# LOGO_LED_board.net
KiCad netlist of a schematic drawn in EAGLE
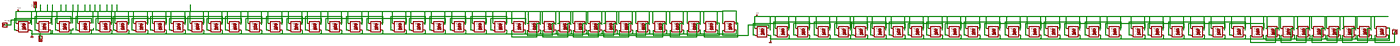
[diagram p0: schematic, sheet 1, overview]
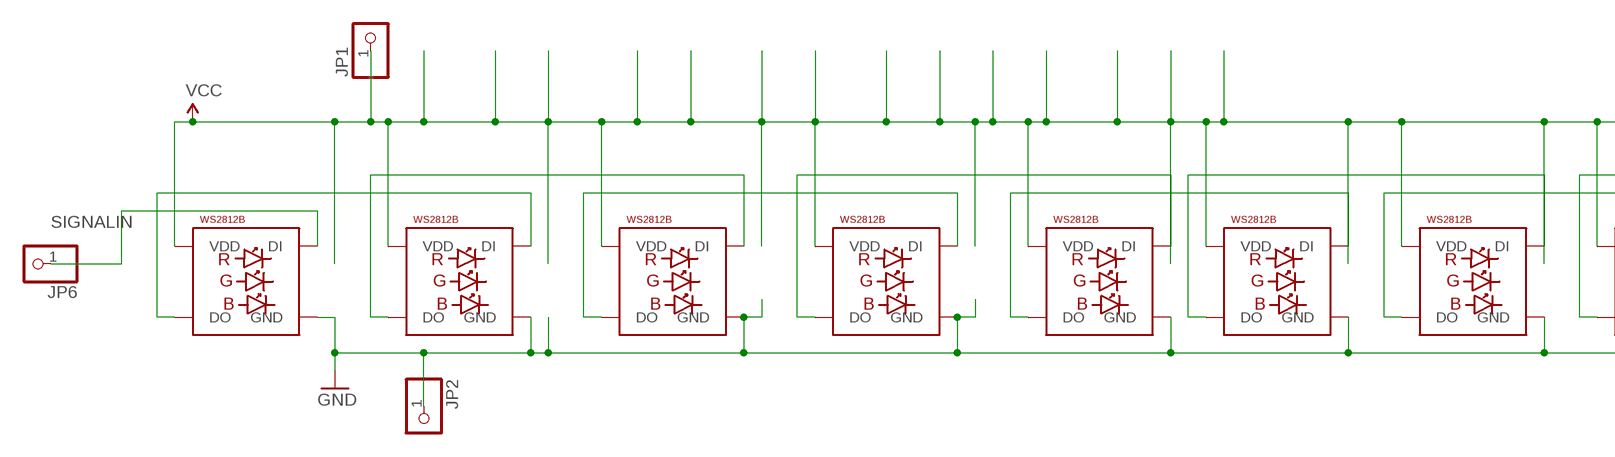
[diagram p1: schematic, sheet 1, part 1 of 8]
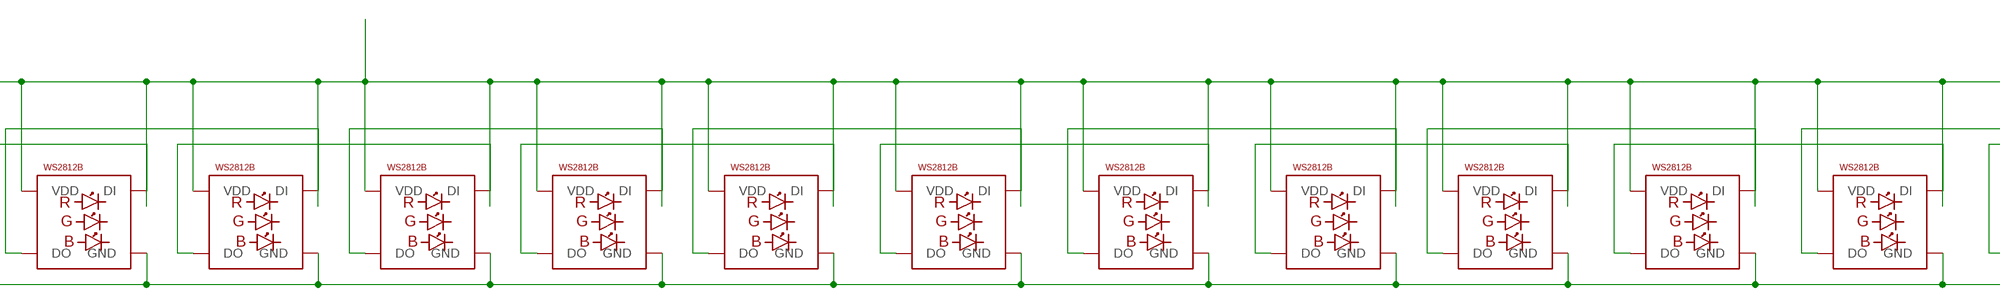
[diagram p2: schematic, sheet 1, part 2 of 8]
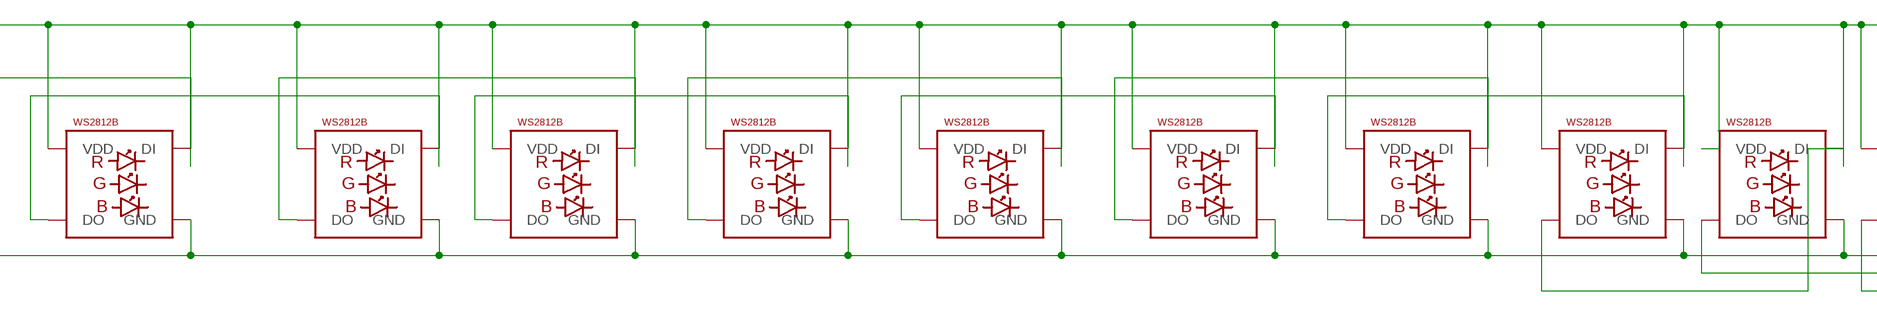
[diagram p3: schematic, sheet 1, part 3 of 8]
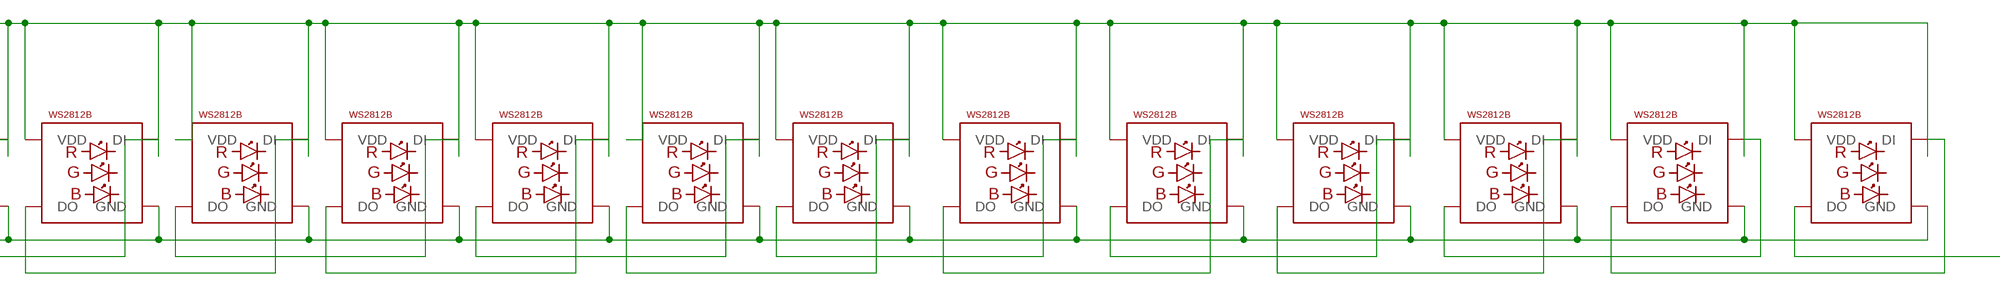
[diagram p4: schematic, sheet 1, part 4 of 8]
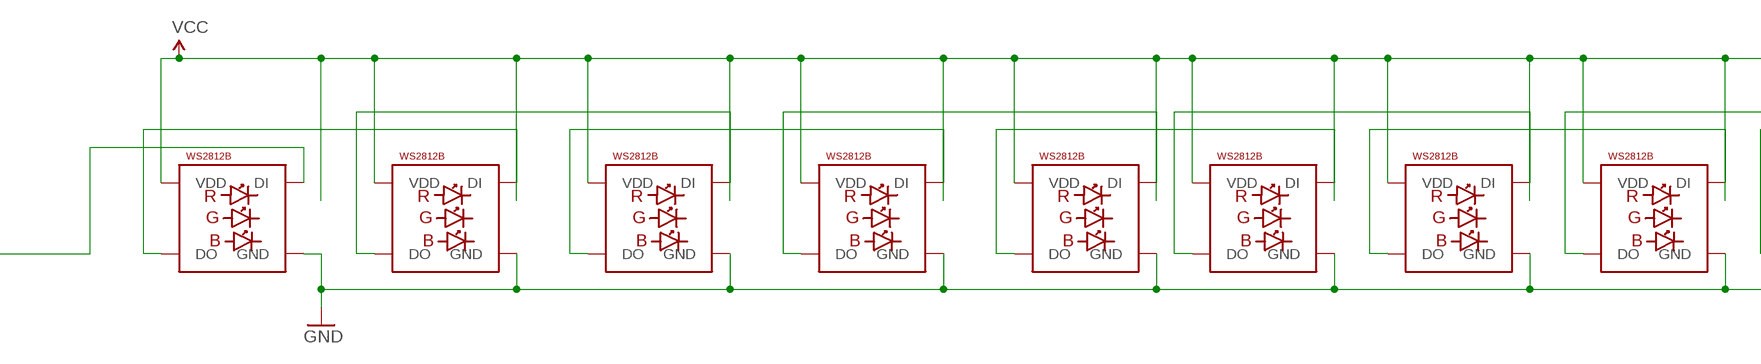
[diagram p5: schematic, sheet 1, part 5 of 8]
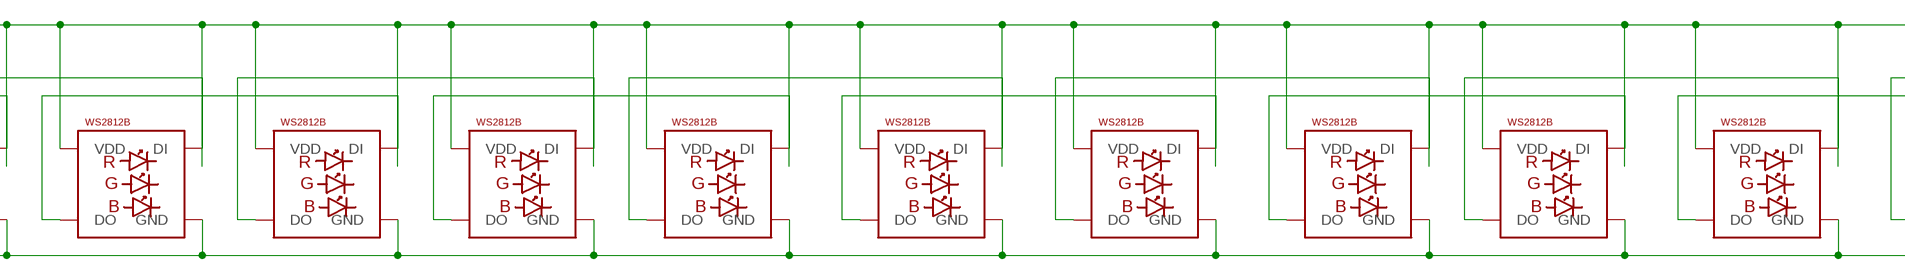
[diagram p6: schematic, sheet 1, part 6 of 8]
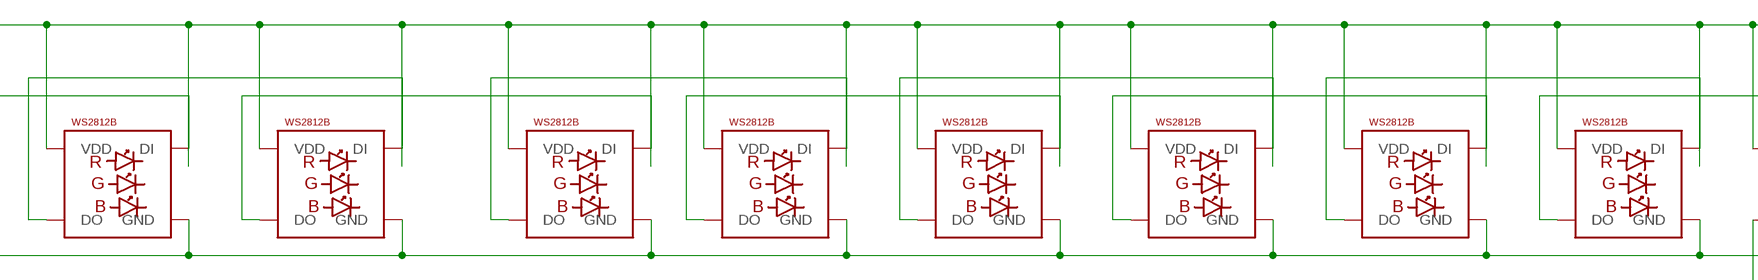
[diagram p7: schematic, sheet 1, part 7 of 8]
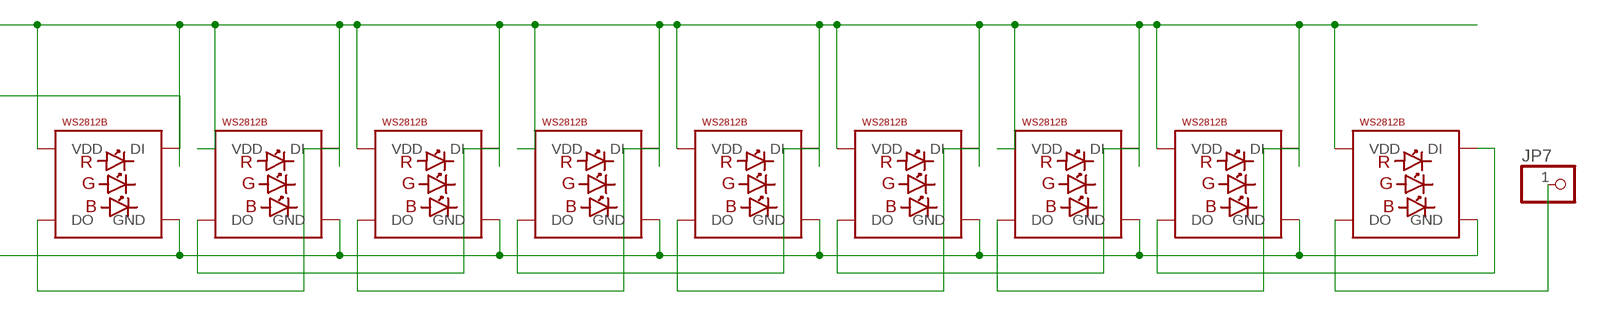
[diagram p8: schematic, sheet 1, part 8 of 8]

(export (version "E")
  (design (tool "Eeschema 10.0.6"))
  (components
    (comp (ref "JP1")
      (value "PINHD-1X1")
      (footprint "eagle-import:1X01")
      (libsource (lib "eagle-import") (part "PINHD-1X1"))
    )
    (comp (ref "JP2")
      (value "PINHD-1X1")
      (footprint "eagle-import:1X01")
      (libsource (lib "eagle-import") (part "PINHD-1X1"))
    )
    (comp (ref "JP6")
      (value "PINHD-1X1")
      (footprint "eagle-import:1X01")
      (libsource (lib "eagle-import") (part "PINHD-1X1"))
    )
    (comp (ref "JP7")
      (value "PINHD-1X1")
      (footprint "eagle-import:1X01")
      (libsource (lib "eagle-import") (part "PINHD-1X1"))
    )
    (comp (ref "LED1")
      (value "WS2812B5050")
      (footprint "eagle-import:WS2812B")
      (libsource (lib "eagle-import") (part "WS2812B5050"))
    )
    (comp (ref "LED2")
      (value "WS2812B5050")
      (footprint "eagle-import:WS2812B")
      (libsource (lib "eagle-import") (part "WS2812B5050"))
    )
    (comp (ref "LED3")
      (value "WS2812B5050")
      (footprint "eagle-import:WS2812B")
      (libsource (lib "eagle-import") (part "WS2812B5050"))
    )
    (comp (ref "LED4")
      (value "WS2812B5050")
      (footprint "eagle-import:WS2812B")
      (libsource (lib "eagle-import") (part "WS2812B5050"))
    )
    (comp (ref "LED5")
      (value "WS2812B5050")
      (footprint "eagle-import:WS2812B")
      (libsource (lib "eagle-import") (part "WS2812B5050"))
    )
    (comp (ref "LED6")
      (value "WS2812B5050")
      (footprint "eagle-import:WS2812B")
      (libsource (lib "eagle-import") (part "WS2812B5050"))
    )
    (comp (ref "LED7")
      (value "WS2812B5050")
      (footprint "eagle-import:WS2812B")
      (libsource (lib "eagle-import") (part "WS2812B5050"))
    )
    (comp (ref "LED8")
      (value "WS2812B5050")
      (footprint "eagle-import:WS2812B")
      (libsource (lib "eagle-import") (part "WS2812B5050"))
    )
    (comp (ref "LED9")
      (value "WS2812B5050")
      (footprint "eagle-import:WS2812B")
      (libsource (lib "eagle-import") (part "WS2812B5050"))
    )
    (comp (ref "LED10")
      (value "WS2812B5050")
      (footprint "eagle-import:WS2812B")
      (libsource (lib "eagle-import") (part "WS2812B5050"))
    )
    (comp (ref "LED11")
      (value "WS2812B5050")
      (footprint "eagle-import:WS2812B")
      (libsource (lib "eagle-import") (part "WS2812B5050"))
    )
    (comp (ref "LED12")
      (value "WS2812B5050")
      (footprint "eagle-import:WS2812B")
      (libsource (lib "eagle-import") (part "WS2812B5050"))
    )
    (comp (ref "LED13")
      (value "WS2812B5050")
      (footprint "eagle-import:WS2812B")
      (libsource (lib "eagle-import") (part "WS2812B5050"))
    )
    (comp (ref "LED14")
      (value "WS2812B5050")
      (footprint "eagle-import:WS2812B")
      (libsource (lib "eagle-import") (part "WS2812B5050"))
    )
    (comp (ref "LED15")
      (value "WS2812B5050")
      (footprint "eagle-import:WS2812B")
      (libsource (lib "eagle-import") (part "WS2812B5050"))
    )
    (comp (ref "LED16")
      (value "WS2812B5050")
      (footprint "eagle-import:WS2812B")
      (libsource (lib "eagle-import") (part "WS2812B5050"))
    )
    (comp (ref "LED17")
      (value "WS2812B5050")
      (footprint "eagle-import:WS2812B")
      (libsource (lib "eagle-import") (part "WS2812B5050"))
    )
    (comp (ref "LED18")
      (value "WS2812B5050")
      (footprint "eagle-import:WS2812B")
      (libsource (lib "eagle-import") (part "WS2812B5050"))
    )
    (comp (ref "LED19")
      (value "WS2812B5050")
      (footprint "eagle-import:WS2812B")
      (libsource (lib "eagle-import") (part "WS2812B5050"))
    )
    (comp (ref "LED20")
      (value "WS2812B5050")
      (footprint "eagle-import:WS2812B")
      (libsource (lib "eagle-import") (part "WS2812B5050"))
    )
    (comp (ref "LED21")
      (value "WS2812B5050")
      (footprint "eagle-import:WS2812B")
      (libsource (lib "eagle-import") (part "WS2812B5050"))
    )
    (comp (ref "LED22")
      (value "WS2812B5050")
      (footprint "eagle-import:WS2812B")
      (libsource (lib "eagle-import") (part "WS2812B5050"))
    )
    (comp (ref "LED23")
      (value "WS2812B5050")
      (footprint "eagle-import:WS2812B")
      (libsource (lib "eagle-import") (part "WS2812B5050"))
    )
    (comp (ref "LED24")
      (value "WS2812B5050")
      (footprint "eagle-import:WS2812B")
      (libsource (lib "eagle-import") (part "WS2812B5050"))
    )
    (comp (ref "LED25")
      (value "WS2812B5050")
      (footprint "eagle-import:WS2812B")
      (libsource (lib "eagle-import") (part "WS2812B5050"))
    )
    (comp (ref "LED26")
      (value "WS2812B5050")
      (footprint "eagle-import:WS2812B")
      (libsource (lib "eagle-import") (part "WS2812B5050"))
    )
    (comp (ref "LED27")
      (value "WS2812B5050")
      (footprint "eagle-import:WS2812B")
      (libsource (lib "eagle-import") (part "WS2812B5050"))
    )
    (comp (ref "LED28")
      (value "WS2812B5050")
      (footprint "eagle-import:WS2812B")
      (libsource (lib "eagle-import") (part "WS2812B5050"))
    )
    (comp (ref "LED29")
      (value "WS2812B5050")
      (footprint "eagle-import:WS2812B")
      (libsource (lib "eagle-import") (part "WS2812B5050"))
    )
    (comp (ref "LED30")
      (value "WS2812B5050")
      (footprint "eagle-import:WS2812B")
      (libsource (lib "eagle-import") (part "WS2812B5050"))
    )
    (comp (ref "LED31")
      (value "WS2812B5050")
      (footprint "eagle-import:WS2812B")
      (libsource (lib "eagle-import") (part "WS2812B5050"))
    )
    (comp (ref "LED32")
      (value "WS2812B5050")
      (footprint "eagle-import:WS2812B")
      (libsource (lib "eagle-import") (part "WS2812B5050"))
    )
    (comp (ref "LED33")
      (value "WS2812B5050")
      (footprint "eagle-import:WS2812B")
      (libsource (lib "eagle-import") (part "WS2812B5050"))
    )
    (comp (ref "LED34")
      (value "WS2812B5050")
      (footprint "eagle-import:WS2812B")
      (libsource (lib "eagle-import") (part "WS2812B5050"))
    )
    (comp (ref "LED35")
      (value "WS2812B5050")
      (footprint "eagle-import:WS2812B")
      (libsource (lib "eagle-import") (part "WS2812B5050"))
    )
    (comp (ref "LED36")
      (value "WS2812B5050")
      (footprint "eagle-import:WS2812B")
      (libsource (lib "eagle-import") (part "WS2812B5050"))
    )
    (comp (ref "LED37")
      (value "WS2812B5050")
      (footprint "eagle-import:WS2812B")
      (libsource (lib "eagle-import") (part "WS2812B5050"))
    )
    (comp (ref "LED38")
      (value "WS2812B5050")
      (footprint "eagle-import:WS2812B")
      (libsource (lib "eagle-import") (part "WS2812B5050"))
    )
    (comp (ref "LED39")
      (value "WS2812B5050")
      (footprint "eagle-import:WS2812B")
      (libsource (lib "eagle-import") (part "WS2812B5050"))
    )
    (comp (ref "LED40")
      (value "WS2812B5050")
      (footprint "eagle-import:WS2812B")
      (libsource (lib "eagle-import") (part "WS2812B5050"))
    )
    (comp (ref "LED41")
      (value "WS2812B5050")
      (footprint "eagle-import:WS2812B")
      (libsource (lib "eagle-import") (part "WS2812B5050"))
    )
    (comp (ref "LED42")
      (value "WS2812B5050")
      (footprint "eagle-import:WS2812B")
      (libsource (lib "eagle-import") (part "WS2812B5050"))
    )
    (comp (ref "LED43")
      (value "WS2812B5050")
      (footprint "eagle-import:WS2812B")
      (libsource (lib "eagle-import") (part "WS2812B5050"))
    )
    (comp (ref "LED44")
      (value "WS2812B5050")
      (footprint "eagle-import:WS2812B")
      (libsource (lib "eagle-import") (part "WS2812B5050"))
    )
    (comp (ref "LED45")
      (value "WS2812B5050")
      (footprint "eagle-import:WS2812B")
      (libsource (lib "eagle-import") (part "WS2812B5050"))
    )
    (comp (ref "LED46")
      (value "WS2812B5050")
      (footprint "eagle-import:WS2812B")
      (libsource (lib "eagle-import") (part "WS2812B5050"))
    )
    (comp (ref "LED47")
      (value "WS2812B5050")
      (footprint "eagle-import:WS2812B")
      (libsource (lib "eagle-import") (part "WS2812B5050"))
    )
    (comp (ref "LED48")
      (value "WS2812B5050")
      (footprint "eagle-import:WS2812B")
      (libsource (lib "eagle-import") (part "WS2812B5050"))
    )
    (comp (ref "LED49")
      (value "WS2812B5050")
      (footprint "eagle-import:WS2812B")
      (libsource (lib "eagle-import") (part "WS2812B5050"))
    )
    (comp (ref "LED50")
      (value "WS2812B5050")
      (footprint "eagle-import:WS2812B")
      (libsource (lib "eagle-import") (part "WS2812B5050"))
    )
    (comp (ref "LED51")
      (value "WS2812B5050")
      (footprint "eagle-import:WS2812B")
      (libsource (lib "eagle-import") (part "WS2812B5050"))
    )
    (comp (ref "LED52")
      (value "WS2812B5050")
      (footprint "eagle-import:WS2812B")
      (libsource (lib "eagle-import") (part "WS2812B5050"))
    )
    (comp (ref "LED53")
      (value "WS2812B5050")
      (footprint "eagle-import:WS2812B")
      (libsource (lib "eagle-import") (part "WS2812B5050"))
    )
    (comp (ref "LED54")
      (value "WS2812B5050")
      (footprint "eagle-import:WS2812B")
      (libsource (lib "eagle-import") (part "WS2812B5050"))
    )
    (comp (ref "LED55")
      (value "WS2812B5050")
      (footprint "eagle-import:WS2812B")
      (libsource (lib "eagle-import") (part "WS2812B5050"))
    )
    (comp (ref "LED56")
      (value "WS2812B5050")
      (footprint "eagle-import:WS2812B")
      (libsource (lib "eagle-import") (part "WS2812B5050"))
    )
    (comp (ref "LED57")
      (value "WS2812B5050")
      (footprint "eagle-import:WS2812B")
      (libsource (lib "eagle-import") (part "WS2812B5050"))
    )
    (comp (ref "LED58")
      (value "WS2812B5050")
      (footprint "eagle-import:WS2812B")
      (libsource (lib "eagle-import") (part "WS2812B5050"))
    )
    (comp (ref "LED59")
      (value "WS2812B5050")
      (footprint "eagle-import:WS2812B")
      (libsource (lib "eagle-import") (part "WS2812B5050"))
    )
    (comp (ref "LED60")
      (value "WS2812B5050")
      (footprint "eagle-import:WS2812B")
      (libsource (lib "eagle-import") (part "WS2812B5050"))
    )
    (comp (ref "LED61")
      (value "WS2812B5050")
      (footprint "eagle-import:WS2812B")
      (libsource (lib "eagle-import") (part "WS2812B5050"))
    )
    (comp (ref "LED62")
      (value "WS2812B5050")
      (footprint "eagle-import:WS2812B")
      (libsource (lib "eagle-import") (part "WS2812B5050"))
    )
    (comp (ref "LED63")
      (value "WS2812B5050")
      (footprint "eagle-import:WS2812B")
      (libsource (lib "eagle-import") (part "WS2812B5050"))
    )
    (comp (ref "LED64")
      (value "WS2812B5050")
      (footprint "eagle-import:WS2812B")
      (libsource (lib "eagle-import") (part "WS2812B5050"))
    )
    (comp (ref "LED65")
      (value "WS2812B5050")
      (footprint "eagle-import:WS2812B")
      (libsource (lib "eagle-import") (part "WS2812B5050"))
    )
    (comp (ref "LED66")
      (value "WS2812B5050")
      (footprint "eagle-import:WS2812B")
      (libsource (lib "eagle-import") (part "WS2812B5050"))
    )
    (comp (ref "LED67")
      (value "WS2812B5050")
      (footprint "eagle-import:WS2812B")
      (libsource (lib "eagle-import") (part "WS2812B5050"))
    )
    (comp (ref "LED68")
      (value "WS2812B5050")
      (footprint "eagle-import:WS2812B")
      (libsource (lib "eagle-import") (part "WS2812B5050"))
    )
    (comp (ref "LED69")
      (value "WS2812B5050")
      (footprint "eagle-import:WS2812B")
      (libsource (lib "eagle-import") (part "WS2812B5050"))
    )
    (comp (ref "LED70")
      (value "WS2812B5050")
      (footprint "eagle-import:WS2812B")
      (libsource (lib "eagle-import") (part "WS2812B5050"))
    )
    (comp (ref "LED71")
      (value "WS2812B5050")
      (footprint "eagle-import:WS2812B")
      (libsource (lib "eagle-import") (part "WS2812B5050"))
    )
    (comp (ref "LED72")
      (value "WS2812B5050")
      (footprint "eagle-import:WS2812B")
      (libsource (lib "eagle-import") (part "WS2812B5050"))
    )
    (comp (ref "LED73")
      (value "WS2812B5050")
      (footprint "eagle-import:WS2812B")
      (libsource (lib "eagle-import") (part "WS2812B5050"))
    )
  )
  (nets
    (net (code "1") (name "/SIGNALIN") (class "Default")
      (node (ref "JP6") (pin "1") (pinfunction "1_1") (pintype "passive"))
      (node (ref "LED1") (pin "4-DIN") (pinfunction "DI_4-DIN") (pintype "input"))
    )
    (net (code "2") (name "GND") (class "Default")
      (node (ref "JP2") (pin "1") (pinfunction "1_1") (pintype "passive"))
      (node (ref "LED1") (pin "3-GND") (pinfunction "GND_3-GND") (pintype "power_in"))
      (node (ref "LED10") (pin "3-GND") (pinfunction "GND_3-GND") (pintype "power_in"))
      (node (ref "LED11") (pin "3-GND") (pinfunction "GND_3-GND") (pintype "power_in"))
      (node (ref "LED12") (pin "3-GND") (pinfunction "GND_3-GND") (pintype "power_in"))
      (node (ref "LED13") (pin "3-GND") (pinfunction "GND_3-GND") (pintype "power_in"))
      (node (ref "LED14") (pin "3-GND") (pinfunction "GND_3-GND") (pintype "power_in"))
      (node (ref "LED15") (pin "3-GND") (pinfunction "GND_3-GND") (pintype "power_in"))
      (node (ref "LED16") (pin "3-GND") (pinfunction "GND_3-GND") (pintype "power_in"))
      (node (ref "LED17") (pin "3-GND") (pinfunction "GND_3-GND") (pintype "power_in"))
      (node (ref "LED18") (pin "3-GND") (pinfunction "GND_3-GND") (pintype "power_in"))
      (node (ref "LED19") (pin "3-GND") (pinfunction "GND_3-GND") (pintype "power_in"))
      (node (ref "LED2") (pin "3-GND") (pinfunction "GND_3-GND") (pintype "power_in"))
      (node (ref "LED20") (pin "3-GND") (pinfunction "GND_3-GND") (pintype "power_in"))
      (node (ref "LED21") (pin "3-GND") (pinfunction "GND_3-GND") (pintype "power_in"))
      (node (ref "LED22") (pin "3-GND") (pinfunction "GND_3-GND") (pintype "power_in"))
      (node (ref "LED23") (pin "3-GND") (pinfunction "GND_3-GND") (pintype "power_in"))
      (node (ref "LED24") (pin "3-GND") (pinfunction "GND_3-GND") (pintype "power_in"))
      (node (ref "LED25") (pin "3-GND") (pinfunction "GND_3-GND") (pintype "power_in"))
      (node (ref "LED26") (pin "3-GND") (pinfunction "GND_3-GND") (pintype "power_in"))
      (node (ref "LED27") (pin "3-GND") (pinfunction "GND_3-GND") (pintype "power_in"))
      (node (ref "LED28") (pin "3-GND") (pinfunction "GND_3-GND") (pintype "power_in"))
      (node (ref "LED29") (pin "3-GND") (pinfunction "GND_3-GND") (pintype "power_in"))
      (node (ref "LED3") (pin "3-GND") (pinfunction "GND_3-GND") (pintype "power_in"))
      (node (ref "LED30") (pin "3-GND") (pinfunction "GND_3-GND") (pintype "power_in"))
      (node (ref "LED31") (pin "3-GND") (pinfunction "GND_3-GND") (pintype "power_in"))
      (node (ref "LED32") (pin "3-GND") (pinfunction "GND_3-GND") (pintype "power_in"))
      (node (ref "LED33") (pin "3-GND") (pinfunction "GND_3-GND") (pintype "power_in"))
      (node (ref "LED34") (pin "3-GND") (pinfunction "GND_3-GND") (pintype "power_in"))
      (node (ref "LED35") (pin "3-GND") (pinfunction "GND_3-GND") (pintype "power_in"))
      (node (ref "LED36") (pin "3-GND") (pinfunction "GND_3-GND") (pintype "power_in"))
      (node (ref "LED37") (pin "3-GND") (pinfunction "GND_3-GND") (pintype "power_in"))
      (node (ref "LED38") (pin "3-GND") (pinfunction "GND_3-GND") (pintype "power_in"))
      (node (ref "LED39") (pin "3-GND") (pinfunction "GND_3-GND") (pintype "power_in"))
      (node (ref "LED4") (pin "3-GND") (pinfunction "GND_3-GND") (pintype "power_in"))
      (node (ref "LED40") (pin "3-GND") (pinfunction "GND_3-GND") (pintype "power_in"))
      (node (ref "LED41") (pin "3-GND") (pinfunction "GND_3-GND") (pintype "power_in"))
      (node (ref "LED42") (pin "3-GND") (pinfunction "GND_3-GND") (pintype "power_in"))
      (node (ref "LED43") (pin "3-GND") (pinfunction "GND_3-GND") (pintype "power_in"))
      (node (ref "LED44") (pin "3-GND") (pinfunction "GND_3-GND") (pintype "power_in"))
      (node (ref "LED45") (pin "3-GND") (pinfunction "GND_3-GND") (pintype "power_in"))
      (node (ref "LED46") (pin "3-GND") (pinfunction "GND_3-GND") (pintype "power_in"))
      (node (ref "LED47") (pin "3-GND") (pinfunction "GND_3-GND") (pintype "power_in"))
      (node (ref "LED48") (pin "3-GND") (pinfunction "GND_3-GND") (pintype "power_in"))
      (node (ref "LED49") (pin "3-GND") (pinfunction "GND_3-GND") (pintype "power_in"))
      (node (ref "LED5") (pin "3-GND") (pinfunction "GND_3-GND") (pintype "power_in"))
      (node (ref "LED50") (pin "3-GND") (pinfunction "GND_3-GND") (pintype "power_in"))
      (node (ref "LED51") (pin "3-GND") (pinfunction "GND_3-GND") (pintype "power_in"))
      (node (ref "LED52") (pin "3-GND") (pinfunction "GND_3-GND") (pintype "power_in"))
      (node (ref "LED53") (pin "3-GND") (pinfunction "GND_3-GND") (pintype "power_in"))
      (node (ref "LED54") (pin "3-GND") (pinfunction "GND_3-GND") (pintype "power_in"))
      (node (ref "LED55") (pin "3-GND") (pinfunction "GND_3-GND") (pintype "power_in"))
      (node (ref "LED56") (pin "3-GND") (pinfunction "GND_3-GND") (pintype "power_in"))
      (node (ref "LED57") (pin "3-GND") (pinfunction "GND_3-GND") (pintype "power_in"))
      (node (ref "LED58") (pin "3-GND") (pinfunction "GND_3-GND") (pintype "power_in"))
      (node (ref "LED59") (pin "3-GND") (pinfunction "GND_3-GND") (pintype "power_in"))
      (node (ref "LED6") (pin "3-GND") (pinfunction "GND_3-GND") (pintype "power_in"))
      (node (ref "LED60") (pin "3-GND") (pinfunction "GND_3-GND") (pintype "power_in"))
      (node (ref "LED61") (pin "3-GND") (pinfunction "GND_3-GND") (pintype "power_in"))
      (node (ref "LED62") (pin "3-GND") (pinfunction "GND_3-GND") (pintype "power_in"))
      (node (ref "LED63") (pin "3-GND") (pinfunction "GND_3-GND") (pintype "power_in"))
      (node (ref "LED64") (pin "3-GND") (pinfunction "GND_3-GND") (pintype "power_in"))
      (node (ref "LED65") (pin "3-GND") (pinfunction "GND_3-GND") (pintype "power_in"))
      (node (ref "LED66") (pin "3-GND") (pinfunction "GND_3-GND") (pintype "power_in"))
      (node (ref "LED67") (pin "3-GND") (pinfunction "GND_3-GND") (pintype "power_in"))
      (node (ref "LED68") (pin "3-GND") (pinfunction "GND_3-GND") (pintype "power_in"))
      (node (ref "LED69") (pin "3-GND") (pinfunction "GND_3-GND") (pintype "power_in"))
      (node (ref "LED7") (pin "3-GND") (pinfunction "GND_3-GND") (pintype "power_in"))
      (node (ref "LED70") (pin "3-GND") (pinfunction "GND_3-GND") (pintype "power_in"))
      (node (ref "LED71") (pin "3-GND") (pinfunction "GND_3-GND") (pintype "power_in"))
      (node (ref "LED72") (pin "3-GND") (pinfunction "GND_3-GND") (pintype "power_in"))
      (node (ref "LED73") (pin "3-GND") (pinfunction "GND_3-GND") (pintype "power_in"))
      (node (ref "LED8") (pin "3-GND") (pinfunction "GND_3-GND") (pintype "power_in"))
      (node (ref "LED9") (pin "3-GND") (pinfunction "GND_3-GND") (pintype "power_in"))
    )
    (net (code "3") (name "Net-(LED1-DO)") (class "Default")
      (node (ref "LED1") (pin "2-DOUT") (pinfunction "DO_2-DOUT") (pintype "output"))
      (node (ref "LED2") (pin "4-DIN") (pinfunction "DI_4-DIN") (pintype "input"))
    )
    (net (code "4") (name "Net-(LED2-DO)") (class "Default")
      (node (ref "LED2") (pin "2-DOUT") (pinfunction "DO_2-DOUT") (pintype "output"))
      (node (ref "LED3") (pin "4-DIN") (pinfunction "DI_4-DIN") (pintype "input"))
    )
    (net (code "5") (name "Net-(LED3-DO)") (class "Default")
      (node (ref "LED3") (pin "2-DOUT") (pinfunction "DO_2-DOUT") (pintype "output"))
      (node (ref "LED4") (pin "4-DIN") (pinfunction "DI_4-DIN") (pintype "input"))
    )
    (net (code "6") (name "Net-(LED4-DO)") (class "Default")
      (node (ref "LED4") (pin "2-DOUT") (pinfunction "DO_2-DOUT") (pintype "output"))
      (node (ref "LED5") (pin "4-DIN") (pinfunction "DI_4-DIN") (pintype "input"))
    )
    (net (code "7") (name "Net-(LED5-DO)") (class "Default")
      (node (ref "LED5") (pin "2-DOUT") (pinfunction "DO_2-DOUT") (pintype "output"))
      (node (ref "LED6") (pin "4-DIN") (pinfunction "DI_4-DIN") (pintype "input"))
    )
    (net (code "8") (name "Net-(LED6-DO)") (class "Default")
      (node (ref "LED6") (pin "2-DOUT") (pinfunction "DO_2-DOUT") (pintype "output"))
      (node (ref "LED7") (pin "4-DIN") (pinfunction "DI_4-DIN") (pintype "input"))
    )
    (net (code "9") (name "Net-(LED7-DO)") (class "Default")
      (node (ref "LED7") (pin "2-DOUT") (pinfunction "DO_2-DOUT") (pintype "output"))
      (node (ref "LED8") (pin "4-DIN") (pinfunction "DI_4-DIN") (pintype "input"))
    )
    (net (code "10") (name "Net-(LED8-DO)") (class "Default")
      (node (ref "LED8") (pin "2-DOUT") (pinfunction "DO_2-DOUT") (pintype "output"))
      (node (ref "LED9") (pin "4-DIN") (pinfunction "DI_4-DIN") (pintype "input"))
    )
    (net (code "11") (name "Net-(LED10-DI)") (class "Default")
      (node (ref "LED10") (pin "4-DIN") (pinfunction "DI_4-DIN") (pintype "input"))
      (node (ref "LED9") (pin "2-DOUT") (pinfunction "DO_2-DOUT") (pintype "output"))
    )
    (net (code "12") (name "Net-(LED10-DO)") (class "Default")
      (node (ref "LED10") (pin "2-DOUT") (pinfunction "DO_2-DOUT") (pintype "output"))
      (node (ref "LED11") (pin "4-DIN") (pinfunction "DI_4-DIN") (pintype "input"))
    )
    (net (code "13") (name "Net-(LED11-DO)") (class "Default")
      (node (ref "LED11") (pin "2-DOUT") (pinfunction "DO_2-DOUT") (pintype "output"))
      (node (ref "LED12") (pin "4-DIN") (pinfunction "DI_4-DIN") (pintype "input"))
    )
    (net (code "14") (name "Net-(LED12-DO)") (class "Default")
      (node (ref "LED12") (pin "2-DOUT") (pinfunction "DO_2-DOUT") (pintype "output"))
      (node (ref "LED13") (pin "4-DIN") (pinfunction "DI_4-DIN") (pintype "input"))
    )
    (net (code "15") (name "Net-(LED13-DO)") (class "Default")
      (node (ref "LED13") (pin "2-DOUT") (pinfunction "DO_2-DOUT") (pintype "output"))
      (node (ref "LED14") (pin "4-DIN") (pinfunction "DI_4-DIN") (pintype "input"))
    )
    (net (code "16") (name "Net-(LED14-DO)") (class "Default")
      (node (ref "LED14") (pin "2-DOUT") (pinfunction "DO_2-DOUT") (pintype "output"))
      (node (ref "LED15") (pin "4-DIN") (pinfunction "DI_4-DIN") (pintype "input"))
    )
    (net (code "17") (name "Net-(LED15-DO)") (class "Default")
      (node (ref "LED15") (pin "2-DOUT") (pinfunction "DO_2-DOUT") (pintype "output"))
      (node (ref "LED16") (pin "4-DIN") (pinfunction "DI_4-DIN") (pintype "input"))
    )
    (net (code "18") (name "Net-(LED16-DO)") (class "Default")
      (node (ref "LED16") (pin "2-DOUT") (pinfunction "DO_2-DOUT") (pintype "output"))
      (node (ref "LED17") (pin "4-DIN") (pinfunction "DI_4-DIN") (pintype "input"))
    )
    (net (code "19") (name "Net-(LED17-DO)") (class "Default")
      (node (ref "LED17") (pin "2-DOUT") (pinfunction "DO_2-DOUT") (pintype "output"))
      (node (ref "LED18") (pin "4-DIN") (pinfunction "DI_4-DIN") (pintype "input"))
    )
    (net (code "20") (name "Net-(LED18-DO)") (class "Default")
      (node (ref "LED18") (pin "2-DOUT") (pinfunction "DO_2-DOUT") (pintype "output"))
      (node (ref "LED19") (pin "4-DIN") (pinfunction "DI_4-DIN") (pintype "input"))
    )
    (net (code "21") (name "Net-(LED19-DO)") (class "Default")
      (node (ref "LED19") (pin "2-DOUT") (pinfunction "DO_2-DOUT") (pintype "output"))
      (node (ref "LED20") (pin "4-DIN") (pinfunction "DI_4-DIN") (pintype "input"))
    )
    (net (code "22") (name "Net-(LED20-DO)") (class "Default")
      (node (ref "LED20") (pin "2-DOUT") (pinfunction "DO_2-DOUT") (pintype "output"))
      (node (ref "LED21") (pin "4-DIN") (pinfunction "DI_4-DIN") (pintype "input"))
    )
    (net (code "23") (name "Net-(LED21-DO)") (class "Default")
      (node (ref "LED21") (pin "2-DOUT") (pinfunction "DO_2-DOUT") (pintype "output"))
      (node (ref "LED22") (pin "4-DIN") (pinfunction "DI_4-DIN") (pintype "input"))
    )
    (net (code "24") (name "Net-(LED22-DO)") (class "Default")
      (node (ref "LED22") (pin "2-DOUT") (pinfunction "DO_2-DOUT") (pintype "output"))
      (node (ref "LED23") (pin "4-DIN") (pinfunction "DI_4-DIN") (pintype "input"))
    )
    (net (code "25") (name "Net-(LED23-DO)") (class "Default")
      (node (ref "LED23") (pin "2-DOUT") (pinfunction "DO_2-DOUT") (pintype "output"))
      (node (ref "LED24") (pin "4-DIN") (pinfunction "DI_4-DIN") (pintype "input"))
    )
    (net (code "26") (name "Net-(LED24-DO)") (class "Default")
      (node (ref "LED24") (pin "2-DOUT") (pinfunction "DO_2-DOUT") (pintype "output"))
      (node (ref "LED25") (pin "4-DIN") (pinfunction "DI_4-DIN") (pintype "input"))
    )
    (net (code "27") (name "Net-(LED25-DO)") (class "Default")
      (node (ref "LED25") (pin "2-DOUT") (pinfunction "DO_2-DOUT") (pintype "output"))
      (node (ref "LED26") (pin "4-DIN") (pinfunction "DI_4-DIN") (pintype "input"))
    )
    (net (code "28") (name "Net-(LED26-DO)") (class "Default")
      (node (ref "LED26") (pin "2-DOUT") (pinfunction "DO_2-DOUT") (pintype "output"))
      (node (ref "LED27") (pin "4-DIN") (pinfunction "DI_4-DIN") (pintype "input"))
    )
    (net (code "29") (name "Net-(LED27-DO)") (class "Default")
      (node (ref "LED27") (pin "2-DOUT") (pinfunction "DO_2-DOUT") (pintype "output"))
      (node (ref "LED28") (pin "4-DIN") (pinfunction "DI_4-DIN") (pintype "input"))
    )
    (net (code "30") (name "Net-(LED28-DO)") (class "Default")
      (node (ref "LED28") (pin "2-DOUT") (pinfunction "DO_2-DOUT") (pintype "output"))
      (node (ref "LED29") (pin "4-DIN") (pinfunction "DI_4-DIN") (pintype "input"))
    )
    (net (code "31") (name "Net-(LED29-DO)") (class "Default")
      (node (ref "LED29") (pin "2-DOUT") (pinfunction "DO_2-DOUT") (pintype "output"))
      (node (ref "LED30") (pin "4-DIN") (pinfunction "DI_4-DIN") (pintype "input"))
    )
    (net (code "32") (name "Net-(LED30-DO)") (class "Default")
      (node (ref "LED30") (pin "2-DOUT") (pinfunction "DO_2-DOUT") (pintype "output"))
      (node (ref "LED31") (pin "4-DIN") (pinfunction "DI_4-DIN") (pintype "input"))
    )
    (net (code "33") (name "Net-(LED31-DO)") (class "Default")
      (node (ref "LED31") (pin "2-DOUT") (pinfunction "DO_2-DOUT") (pintype "output"))
      (node (ref "LED32") (pin "4-DIN") (pinfunction "DI_4-DIN") (pintype "input"))
    )
    (net (code "34") (name "Net-(LED32-DO)") (class "Default")
      (node (ref "LED32") (pin "2-DOUT") (pinfunction "DO_2-DOUT") (pintype "output"))
      (node (ref "LED33") (pin "4-DIN") (pinfunction "DI_4-DIN") (pintype "input"))
    )
    (net (code "35") (name "Net-(LED33-DO)") (class "Default")
      (node (ref "LED33") (pin "2-DOUT") (pinfunction "DO_2-DOUT") (pintype "output"))
      (node (ref "LED34") (pin "4-DIN") (pinfunction "DI_4-DIN") (pintype "input"))
    )
    (net (code "36") (name "Net-(LED34-DO)") (class "Default")
      (node (ref "LED34") (pin "2-DOUT") (pinfunction "DO_2-DOUT") (pintype "output"))
      (node (ref "LED35") (pin "4-DIN") (pinfunction "DI_4-DIN") (pintype "input"))
    )
    (net (code "37") (name "Net-(LED35-DO)") (class "Default")
      (node (ref "LED35") (pin "2-DOUT") (pinfunction "DO_2-DOUT") (pintype "output"))
      (node (ref "LED36") (pin "4-DIN") (pinfunction "DI_4-DIN") (pintype "input"))
    )
    (net (code "38") (name "Net-(LED36-DO)") (class "Default")
      (node (ref "LED36") (pin "2-DOUT") (pinfunction "DO_2-DOUT") (pintype "output"))
      (node (ref "LED37") (pin "4-DIN") (pinfunction "DI_4-DIN") (pintype "input"))
    )
    (net (code "39") (name "Net-(LED37-DO)") (class "Default")
      (node (ref "LED37") (pin "2-DOUT") (pinfunction "DO_2-DOUT") (pintype "output"))
      (node (ref "LED38") (pin "4-DIN") (pinfunction "DI_4-DIN") (pintype "input"))
    )
    (net (code "40") (name "Net-(LED38-DO)") (class "Default")
      (node (ref "LED38") (pin "2-DOUT") (pinfunction "DO_2-DOUT") (pintype "output"))
      (node (ref "LED39") (pin "4-DIN") (pinfunction "DI_4-DIN") (pintype "input"))
    )
    (net (code "41") (name "Net-(LED39-DO)") (class "Default")
      (node (ref "LED39") (pin "2-DOUT") (pinfunction "DO_2-DOUT") (pintype "output"))
      (node (ref "LED40") (pin "4-DIN") (pinfunction "DI_4-DIN") (pintype "input"))
    )
    (net (code "42") (name "Net-(LED40-DO)") (class "Default")
      (node (ref "LED40") (pin "2-DOUT") (pinfunction "DO_2-DOUT") (pintype "output"))
      (node (ref "LED41") (pin "4-DIN") (pinfunction "DI_4-DIN") (pintype "input"))
    )
    (net (code "43") (name "Net-(LED41-DO)") (class "Default")
      (node (ref "LED41") (pin "2-DOUT") (pinfunction "DO_2-DOUT") (pintype "output"))
      (node (ref "LED42") (pin "4-DIN") (pinfunction "DI_4-DIN") (pintype "input"))
    )
    (net (code "44") (name "Net-(LED42-DO)") (class "Default")
      (node (ref "LED42") (pin "2-DOUT") (pinfunction "DO_2-DOUT") (pintype "output"))
      (node (ref "LED43") (pin "4-DIN") (pinfunction "DI_4-DIN") (pintype "input"))
    )
    (net (code "45") (name "Net-(LED43-DO)") (class "Default")
      (node (ref "LED43") (pin "2-DOUT") (pinfunction "DO_2-DOUT") (pintype "output"))
      (node (ref "LED44") (pin "4-DIN") (pinfunction "DI_4-DIN") (pintype "input"))
    )
    (net (code "46") (name "Net-(LED44-DO)") (class "Default")
      (node (ref "LED44") (pin "2-DOUT") (pinfunction "DO_2-DOUT") (pintype "output"))
      (node (ref "LED45") (pin "4-DIN") (pinfunction "DI_4-DIN") (pintype "input"))
    )
    (net (code "47") (name "Net-(LED45-DO)") (class "Default")
      (node (ref "LED45") (pin "2-DOUT") (pinfunction "DO_2-DOUT") (pintype "output"))
      (node (ref "LED46") (pin "4-DIN") (pinfunction "DI_4-DIN") (pintype "input"))
    )
    (net (code "48") (name "Net-(LED46-DO)") (class "Default")
      (node (ref "LED46") (pin "2-DOUT") (pinfunction "DO_2-DOUT") (pintype "output"))
      (node (ref "LED47") (pin "4-DIN") (pinfunction "DI_4-DIN") (pintype "input"))
    )
    (net (code "49") (name "Net-(LED47-DO)") (class "Default")
      (node (ref "LED47") (pin "2-DOUT") (pinfunction "DO_2-DOUT") (pintype "output"))
      (node (ref "LED48") (pin "4-DIN") (pinfunction "DI_4-DIN") (pintype "input"))
    )
    (net (code "50") (name "Net-(LED48-DO)") (class "Default")
      (node (ref "LED48") (pin "2-DOUT") (pinfunction "DO_2-DOUT") (pintype "output"))
      (node (ref "LED49") (pin "4-DIN") (pinfunction "DI_4-DIN") (pintype "input"))
    )
    (net (code "51") (name "Net-(LED49-DO)") (class "Default")
      (node (ref "LED49") (pin "2-DOUT") (pinfunction "DO_2-DOUT") (pintype "output"))
      (node (ref "LED50") (pin "4-DIN") (pinfunction "DI_4-DIN") (pintype "input"))
    )
    (net (code "52") (name "Net-(LED50-DO)") (class "Default")
      (node (ref "LED50") (pin "2-DOUT") (pinfunction "DO_2-DOUT") (pintype "output"))
      (node (ref "LED51") (pin "4-DIN") (pinfunction "DI_4-DIN") (pintype "input"))
    )
    (net (code "53") (name "Net-(LED51-DO)") (class "Default")
      (node (ref "LED51") (pin "2-DOUT") (pinfunction "DO_2-DOUT") (pintype "output"))
      (node (ref "LED52") (pin "4-DIN") (pinfunction "DI_4-DIN") (pintype "input"))
    )
    (net (code "54") (name "Net-(LED52-DO)") (class "Default")
      (node (ref "LED52") (pin "2-DOUT") (pinfunction "DO_2-DOUT") (pintype "output"))
      (node (ref "LED53") (pin "4-DIN") (pinfunction "DI_4-DIN") (pintype "input"))
    )
    (net (code "55") (name "Net-(LED53-DO)") (class "Default")
      (node (ref "LED53") (pin "2-DOUT") (pinfunction "DO_2-DOUT") (pintype "output"))
      (node (ref "LED54") (pin "4-DIN") (pinfunction "DI_4-DIN") (pintype "input"))
    )
    (net (code "56") (name "Net-(LED54-DO)") (class "Default")
      (node (ref "LED54") (pin "2-DOUT") (pinfunction "DO_2-DOUT") (pintype "output"))
      (node (ref "LED55") (pin "4-DIN") (pinfunction "DI_4-DIN") (pintype "input"))
    )
    (net (code "57") (name "Net-(LED55-DO)") (class "Default")
      (node (ref "LED55") (pin "2-DOUT") (pinfunction "DO_2-DOUT") (pintype "output"))
      (node (ref "LED56") (pin "4-DIN") (pinfunction "DI_4-DIN") (pintype "input"))
    )
    (net (code "58") (name "Net-(LED56-DO)") (class "Default")
      (node (ref "LED56") (pin "2-DOUT") (pinfunction "DO_2-DOUT") (pintype "output"))
      (node (ref "LED57") (pin "4-DIN") (pinfunction "DI_4-DIN") (pintype "input"))
    )
    (net (code "59") (name "Net-(LED57-DO)") (class "Default")
      (node (ref "LED57") (pin "2-DOUT") (pinfunction "DO_2-DOUT") (pintype "output"))
      (node (ref "LED58") (pin "4-DIN") (pinfunction "DI_4-DIN") (pintype "input"))
    )
    (net (code "60") (name "Net-(LED58-DO)") (class "Default")
      (node (ref "LED58") (pin "2-DOUT") (pinfunction "DO_2-DOUT") (pintype "output"))
      (node (ref "LED59") (pin "4-DIN") (pinfunction "DI_4-DIN") (pintype "input"))
    )
    (net (code "61") (name "Net-(LED59-DO)") (class "Default")
      (node (ref "LED59") (pin "2-DOUT") (pinfunction "DO_2-DOUT") (pintype "output"))
      (node (ref "LED60") (pin "4-DIN") (pinfunction "DI_4-DIN") (pintype "input"))
    )
    (net (code "62") (name "Net-(LED60-DO)") (class "Default")
      (node (ref "LED60") (pin "2-DOUT") (pinfunction "DO_2-DOUT") (pintype "output"))
      (node (ref "LED61") (pin "4-DIN") (pinfunction "DI_4-DIN") (pintype "input"))
    )
    (net (code "63") (name "Net-(LED61-DO)") (class "Default")
      (node (ref "LED61") (pin "2-DOUT") (pinfunction "DO_2-DOUT") (pintype "output"))
      (node (ref "LED62") (pin "4-DIN") (pinfunction "DI_4-DIN") (pintype "input"))
    )
    (net (code "64") (name "Net-(LED62-DO)") (class "Default")
      (node (ref "LED62") (pin "2-DOUT") (pinfunction "DO_2-DOUT") (pintype "output"))
      (node (ref "LED63") (pin "4-DIN") (pinfunction "DI_4-DIN") (pintype "input"))
    )
    (net (code "65") (name "Net-(LED63-DO)") (class "Default")
      (node (ref "LED63") (pin "2-DOUT") (pinfunction "DO_2-DOUT") (pintype "output"))
      (node (ref "LED64") (pin "4-DIN") (pinfunction "DI_4-DIN") (pintype "input"))
    )
    (net (code "66") (name "Net-(LED64-DO)") (class "Default")
      (node (ref "LED64") (pin "2-DOUT") (pinfunction "DO_2-DOUT") (pintype "output"))
      (node (ref "LED65") (pin "4-DIN") (pinfunction "DI_4-DIN") (pintype "input"))
    )
    (net (code "67") (name "Net-(LED65-DO)") (class "Default")
      (node (ref "LED65") (pin "2-DOUT") (pinfunction "DO_2-DOUT") (pintype "output"))
      (node (ref "LED66") (pin "4-DIN") (pinfunction "DI_4-DIN") (pintype "input"))
    )
    (net (code "68") (name "Net-(LED66-DO)") (class "Default")
      (node (ref "LED66") (pin "2-DOUT") (pinfunction "DO_2-DOUT") (pintype "output"))
      (node (ref "LED67") (pin "4-DIN") (pinfunction "DI_4-DIN") (pintype "input"))
    )
    (net (code "69") (name "Net-(LED67-DO)") (class "Default")
      (node (ref "LED67") (pin "2-DOUT") (pinfunction "DO_2-DOUT") (pintype "output"))
      (node (ref "LED68") (pin "4-DIN") (pinfunction "DI_4-DIN") (pintype "input"))
    )
    (net (code "70") (name "Net-(LED68-DO)") (class "Default")
      (node (ref "LED68") (pin "2-DOUT") (pinfunction "DO_2-DOUT") (pintype "output"))
      (node (ref "LED69") (pin "4-DIN") (pinfunction "DI_4-DIN") (pintype "input"))
    )
    (net (code "71") (name "Net-(LED69-DO)") (class "Default")
      (node (ref "LED69") (pin "2-DOUT") (pinfunction "DO_2-DOUT") (pintype "output"))
      (node (ref "LED70") (pin "4-DIN") (pinfunction "DI_4-DIN") (pintype "input"))
    )
    (net (code "72") (name "Net-(LED70-DO)") (class "Default")
      (node (ref "LED70") (pin "2-DOUT") (pinfunction "DO_2-DOUT") (pintype "output"))
      (node (ref "LED71") (pin "4-DIN") (pinfunction "DI_4-DIN") (pintype "input"))
    )
    (net (code "73") (name "Net-(LED71-DO)") (class "Default")
      (node (ref "LED71") (pin "2-DOUT") (pinfunction "DO_2-DOUT") (pintype "output"))
      (node (ref "LED72") (pin "4-DIN") (pinfunction "DI_4-DIN") (pintype "input"))
    )
    (net (code "74") (name "Net-(LED72-DO)") (class "Default")
      (node (ref "LED72") (pin "2-DOUT") (pinfunction "DO_2-DOUT") (pintype "output"))
      (node (ref "LED73") (pin "4-DIN") (pinfunction "DI_4-DIN") (pintype "input"))
    )
    (net (code "75") (name "Net-(LED73-DO)") (class "Default")
      (node (ref "JP7") (pin "1") (pinfunction "1_1") (pintype "passive"))
      (node (ref "LED73") (pin "2-DOUT") (pinfunction "DO_2-DOUT") (pintype "output"))
    )
    (net (code "76") (name "VCC") (class "Default")
      (node (ref "JP1") (pin "1") (pinfunction "1_1") (pintype "passive"))
      (node (ref "LED1") (pin "1-VDD") (pinfunction "VDD_1-VDD") (pintype "power_in"))
      (node (ref "LED10") (pin "1-VDD") (pinfunction "VDD_1-VDD") (pintype "power_in"))
      (node (ref "LED11") (pin "1-VDD") (pinfunction "VDD_1-VDD") (pintype "power_in"))
      (node (ref "LED12") (pin "1-VDD") (pinfunction "VDD_1-VDD") (pintype "power_in"))
      (node (ref "LED13") (pin "1-VDD") (pinfunction "VDD_1-VDD") (pintype "power_in"))
      (node (ref "LED14") (pin "1-VDD") (pinfunction "VDD_1-VDD") (pintype "power_in"))
      (node (ref "LED15") (pin "1-VDD") (pinfunction "VDD_1-VDD") (pintype "power_in"))
      (node (ref "LED16") (pin "1-VDD") (pinfunction "VDD_1-VDD") (pintype "power_in"))
      (node (ref "LED17") (pin "1-VDD") (pinfunction "VDD_1-VDD") (pintype "power_in"))
      (node (ref "LED18") (pin "1-VDD") (pinfunction "VDD_1-VDD") (pintype "power_in"))
      (node (ref "LED19") (pin "1-VDD") (pinfunction "VDD_1-VDD") (pintype "power_in"))
      (node (ref "LED2") (pin "1-VDD") (pinfunction "VDD_1-VDD") (pintype "power_in"))
      (node (ref "LED20") (pin "1-VDD") (pinfunction "VDD_1-VDD") (pintype "power_in"))
      (node (ref "LED21") (pin "1-VDD") (pinfunction "VDD_1-VDD") (pintype "power_in"))
      (node (ref "LED22") (pin "1-VDD") (pinfunction "VDD_1-VDD") (pintype "power_in"))
      (node (ref "LED23") (pin "1-VDD") (pinfunction "VDD_1-VDD") (pintype "power_in"))
      (node (ref "LED24") (pin "1-VDD") (pinfunction "VDD_1-VDD") (pintype "power_in"))
      (node (ref "LED25") (pin "1-VDD") (pinfunction "VDD_1-VDD") (pintype "power_in"))
      (node (ref "LED26") (pin "1-VDD") (pinfunction "VDD_1-VDD") (pintype "power_in"))
      (node (ref "LED27") (pin "1-VDD") (pinfunction "VDD_1-VDD") (pintype "power_in"))
      (node (ref "LED28") (pin "1-VDD") (pinfunction "VDD_1-VDD") (pintype "power_in"))
      (node (ref "LED29") (pin "1-VDD") (pinfunction "VDD_1-VDD") (pintype "power_in"))
      (node (ref "LED3") (pin "1-VDD") (pinfunction "VDD_1-VDD") (pintype "power_in"))
      (node (ref "LED30") (pin "1-VDD") (pinfunction "VDD_1-VDD") (pintype "power_in"))
      (node (ref "LED31") (pin "1-VDD") (pinfunction "VDD_1-VDD") (pintype "power_in"))
      (node (ref "LED32") (pin "1-VDD") (pinfunction "VDD_1-VDD") (pintype "power_in"))
      (node (ref "LED33") (pin "1-VDD") (pinfunction "VDD_1-VDD") (pintype "power_in"))
      (node (ref "LED34") (pin "1-VDD") (pinfunction "VDD_1-VDD") (pintype "power_in"))
      (node (ref "LED35") (pin "1-VDD") (pinfunction "VDD_1-VDD") (pintype "power_in"))
      (node (ref "LED36") (pin "1-VDD") (pinfunction "VDD_1-VDD") (pintype "power_in"))
      (node (ref "LED37") (pin "1-VDD") (pinfunction "VDD_1-VDD") (pintype "power_in"))
      (node (ref "LED38") (pin "1-VDD") (pinfunction "VDD_1-VDD") (pintype "power_in"))
      (node (ref "LED39") (pin "1-VDD") (pinfunction "VDD_1-VDD") (pintype "power_in"))
      (node (ref "LED4") (pin "1-VDD") (pinfunction "VDD_1-VDD") (pintype "power_in"))
      (node (ref "LED40") (pin "1-VDD") (pinfunction "VDD_1-VDD") (pintype "power_in"))
      (node (ref "LED41") (pin "1-VDD") (pinfunction "VDD_1-VDD") (pintype "power_in"))
      (node (ref "LED42") (pin "1-VDD") (pinfunction "VDD_1-VDD") (pintype "power_in"))
      (node (ref "LED43") (pin "1-VDD") (pinfunction "VDD_1-VDD") (pintype "power_in"))
      (node (ref "LED44") (pin "1-VDD") (pinfunction "VDD_1-VDD") (pintype "power_in"))
      (node (ref "LED45") (pin "1-VDD") (pinfunction "VDD_1-VDD") (pintype "power_in"))
      (node (ref "LED46") (pin "1-VDD") (pinfunction "VDD_1-VDD") (pintype "power_in"))
      (node (ref "LED47") (pin "1-VDD") (pinfunction "VDD_1-VDD") (pintype "power_in"))
      (node (ref "LED48") (pin "1-VDD") (pinfunction "VDD_1-VDD") (pintype "power_in"))
      (node (ref "LED49") (pin "1-VDD") (pinfunction "VDD_1-VDD") (pintype "power_in"))
      (node (ref "LED5") (pin "1-VDD") (pinfunction "VDD_1-VDD") (pintype "power_in"))
      (node (ref "LED50") (pin "1-VDD") (pinfunction "VDD_1-VDD") (pintype "power_in"))
      (node (ref "LED51") (pin "1-VDD") (pinfunction "VDD_1-VDD") (pintype "power_in"))
      (node (ref "LED52") (pin "1-VDD") (pinfunction "VDD_1-VDD") (pintype "power_in"))
      (node (ref "LED53") (pin "1-VDD") (pinfunction "VDD_1-VDD") (pintype "power_in"))
      (node (ref "LED54") (pin "1-VDD") (pinfunction "VDD_1-VDD") (pintype "power_in"))
      (node (ref "LED55") (pin "1-VDD") (pinfunction "VDD_1-VDD") (pintype "power_in"))
      (node (ref "LED56") (pin "1-VDD") (pinfunction "VDD_1-VDD") (pintype "power_in"))
      (node (ref "LED57") (pin "1-VDD") (pinfunction "VDD_1-VDD") (pintype "power_in"))
      (node (ref "LED58") (pin "1-VDD") (pinfunction "VDD_1-VDD") (pintype "power_in"))
      (node (ref "LED59") (pin "1-VDD") (pinfunction "VDD_1-VDD") (pintype "power_in"))
      (node (ref "LED6") (pin "1-VDD") (pinfunction "VDD_1-VDD") (pintype "power_in"))
      (node (ref "LED60") (pin "1-VDD") (pinfunction "VDD_1-VDD") (pintype "power_in"))
      (node (ref "LED61") (pin "1-VDD") (pinfunction "VDD_1-VDD") (pintype "power_in"))
      (node (ref "LED62") (pin "1-VDD") (pinfunction "VDD_1-VDD") (pintype "power_in"))
      (node (ref "LED63") (pin "1-VDD") (pinfunction "VDD_1-VDD") (pintype "power_in"))
      (node (ref "LED64") (pin "1-VDD") (pinfunction "VDD_1-VDD") (pintype "power_in"))
      (node (ref "LED65") (pin "1-VDD") (pinfunction "VDD_1-VDD") (pintype "power_in"))
      (node (ref "LED66") (pin "1-VDD") (pinfunction "VDD_1-VDD") (pintype "power_in"))
      (node (ref "LED67") (pin "1-VDD") (pinfunction "VDD_1-VDD") (pintype "power_in"))
      (node (ref "LED68") (pin "1-VDD") (pinfunction "VDD_1-VDD") (pintype "power_in"))
      (node (ref "LED69") (pin "1-VDD") (pinfunction "VDD_1-VDD") (pintype "power_in"))
      (node (ref "LED7") (pin "1-VDD") (pinfunction "VDD_1-VDD") (pintype "power_in"))
      (node (ref "LED70") (pin "1-VDD") (pinfunction "VDD_1-VDD") (pintype "power_in"))
      (node (ref "LED71") (pin "1-VDD") (pinfunction "VDD_1-VDD") (pintype "power_in"))
      (node (ref "LED72") (pin "1-VDD") (pinfunction "VDD_1-VDD") (pintype "power_in"))
      (node (ref "LED73") (pin "1-VDD") (pinfunction "VDD_1-VDD") (pintype "power_in"))
      (node (ref "LED8") (pin "1-VDD") (pinfunction "VDD_1-VDD") (pintype "power_in"))
      (node (ref "LED9") (pin "1-VDD") (pinfunction "VDD_1-VDD") (pintype "power_in"))
    )
  )
)
